# Sheet1.net
KiCad netlist of a schematic drawn in Altium Designer
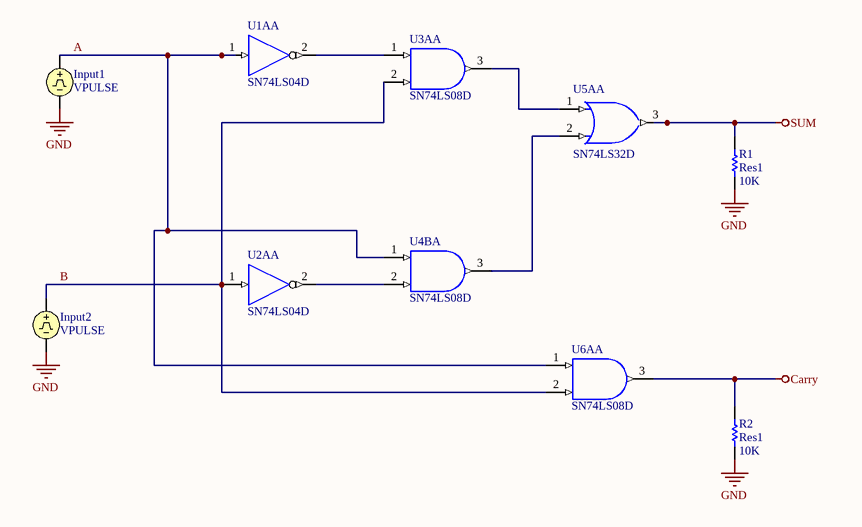
[diagram p0: Sheet1.SchDoc]

(export (version "E")
  (design (tool "Eeschema 10.0.6"))
  (components
    (comp (ref "Input1")
      (value "VPULSE")
      (description "Pulse Voltage Source")
      (fields (field (name "PUBLISHER") "Altium Limited"))
      (libsource (lib "Simulation Sources") (part "VPULSE"))
    )
    (comp (ref "Input2")
      (value "VPULSE")
      (description "Pulse Voltage Source")
      (fields (field (name "PUBLISHER") "Altium Limited"))
      (libsource (lib "Simulation Sources") (part "VPULSE"))
    )
    (comp (ref "R1")
      (value "Res1")
      (footprint "AXIAL-0.3")
      (description "Resistor")
      (fields (field (name "ALTIUM_VALUE") "10K") (field (name "PUBLISHER") "Altium Limited"))
      (libsource (lib "Miscellaneous Devices") (part "Res1"))
    )
    (comp (ref "R2")
      (value "Res1")
      (footprint "AXIAL-0.3")
      (description "Resistor")
      (fields (field (name "ALTIUM_VALUE") "10K") (field (name "PUBLISHER") "Altium Limited"))
      (libsource (lib "Miscellaneous Devices") (part "Res1"))
    )
    (comp (ref "U1A")
      (value "SN74LS04D")
      (footprint "D014_N")
      (description "Hex Inverter")
      (fields (field (name "PUBLISHER") "Altium Limited"))
      (libsource (lib "TI Logic Gate 2") (part "SN74LS04D"))
    )
    (comp (ref "U2A")
      (value "SN74LS04D")
      (footprint "D014_N")
      (description "Hex Inverter")
      (fields (field (name "PUBLISHER") "Altium Limited"))
      (libsource (lib "TI Logic Gate 2") (part "SN74LS04D"))
    )
    (comp (ref "U3A")
      (value "SN74LS08D")
      (footprint "D014_N")
      (description "Quadruple 2-Input Positive-AND Gate")
      (fields (field (name "PUBLISHER") "Altium Limited"))
      (libsource (lib "TI Logic Gate 2") (part "SN74LS08D"))
    )
    (comp (ref "U4B")
      (value "SN74LS08D")
      (footprint "D014_N")
      (description "Quadruple 2-Input Positive-AND Gate")
      (fields (field (name "PUBLISHER") "Altium Limited"))
      (libsource (lib "TI Logic Gate 2") (part "SN74LS08D"))
    )
    (comp (ref "U5A")
      (value "SN74LS32D")
      (footprint "D014_N")
      (description "Quadruple 2-Input Positive-OR Gate")
      (fields (field (name "PUBLISHER") "Altium Limited"))
      (libsource (lib "TI Logic Gate 2") (part "SN74LS32D"))
    )
    (comp (ref "U6A")
      (value "SN74LS08D")
      (footprint "D014_N")
      (description "Quadruple 2-Input Positive-AND Gate")
      (fields (field (name "PUBLISHER") "Altium Limited"))
      (libsource (lib "TI Logic Gate 2") (part "SN74LS08D"))
    )
  )
  (nets
    (net (code "1") (name "/A") (class "Default")
      (node (ref "Input1") (pin "1") (pinfunction "1_1") (pintype "passive"))
      (node (ref "U1A") (pin "1") (pinfunction "A_1") (pintype "input"))
      (node (ref "U4B") (pin "1") (pinfunction "A_1") (pintype "input"))
      (node (ref "U6A") (pin "1") (pinfunction "A_1") (pintype "input"))
    )
    (net (code "2") (name "/B") (class "Default")
      (node (ref "Input2") (pin "1") (pinfunction "1_1") (pintype "passive"))
      (node (ref "U2A") (pin "1") (pinfunction "A_1") (pintype "input"))
      (node (ref "U3A") (pin "2") (pinfunction "B_2") (pintype "input"))
      (node (ref "U6A") (pin "2") (pinfunction "B_2") (pintype "input"))
    )
    (net (code "3") (name "Carry") (class "Default")
      (node (ref "R2") (pin "2") (pinfunction "2_2") (pintype "passive"))
      (node (ref "U6A") (pin "3") (pinfunction "Y_3") (pintype "output"))
    )
    (net (code "4") (name "GND") (class "Default")
      (node (ref "Input1") (pin "2") (pinfunction "2_2") (pintype "passive"))
      (node (ref "Input2") (pin "2") (pinfunction "2_2") (pintype "passive"))
      (node (ref "R1") (pin "1") (pinfunction "1_1") (pintype "passive"))
      (node (ref "R2") (pin "1") (pinfunction "1_1") (pintype "passive"))
      (node (ref "U1A") (pin "7") (pinfunction "GND_7") (pintype "power_in"))
      (node (ref "U2A") (pin "7") (pinfunction "GND_7") (pintype "power_in"))
      (node (ref "U3A") (pin "7") (pinfunction "GND_7") (pintype "power_in"))
      (node (ref "U4B") (pin "7") (pinfunction "GND_7") (pintype "power_in"))
      (node (ref "U5A") (pin "7") (pinfunction "GND_7") (pintype "power_in"))
      (node (ref "U6A") (pin "7") (pinfunction "GND_7") (pintype "power_in"))
    )
    (net (code "5") (name "Net-(U1AA-Y)") (class "Default")
      (node (ref "U1A") (pin "2") (pinfunction "Y_2") (pintype "output"))
      (node (ref "U3A") (pin "1") (pinfunction "A_1") (pintype "input"))
    )
    (net (code "6") (name "Net-(U2AA-Y)") (class "Default")
      (node (ref "U2A") (pin "2") (pinfunction "Y_2") (pintype "output"))
      (node (ref "U4B") (pin "2") (pinfunction "B_2") (pintype "input"))
    )
    (net (code "7") (name "Net-(U3AA-Y)") (class "Default")
      (node (ref "U3A") (pin "3") (pinfunction "Y_3") (pintype "output"))
      (node (ref "U5A") (pin "1") (pinfunction "A_1") (pintype "input"))
    )
    (net (code "8") (name "Net-(U4BA-Y)") (class "Default")
      (node (ref "U4B") (pin "3") (pinfunction "Y_3") (pintype "output"))
      (node (ref "U5A") (pin "2") (pinfunction "B_2") (pintype "input"))
    )
    (net (code "9") (name "SUM") (class "Default")
      (node (ref "R1") (pin "2") (pinfunction "2_2") (pintype "passive"))
      (node (ref "U5A") (pin "3") (pinfunction "Y_3") (pintype "output"))
    )
    (net (code "10") (name "VCC") (class "Default")
      (node (ref "U1A") (pin "14") (pinfunction "VCC_14") (pintype "power_in"))
      (node (ref "U2A") (pin "14") (pinfunction "VCC_14") (pintype "power_in"))
      (node (ref "U3A") (pin "14") (pinfunction "VCC_14") (pintype "power_in"))
      (node (ref "U4B") (pin "14") (pinfunction "VCC_14") (pintype "power_in"))
      (node (ref "U5A") (pin "14") (pinfunction "VCC_14") (pintype "power_in"))
      (node (ref "U6A") (pin "14") (pinfunction "VCC_14") (pintype "power_in"))
    )
  )
)
